# DS157-1_0-B.net
KiCad netlist of a schematic drawn in Altium Designer
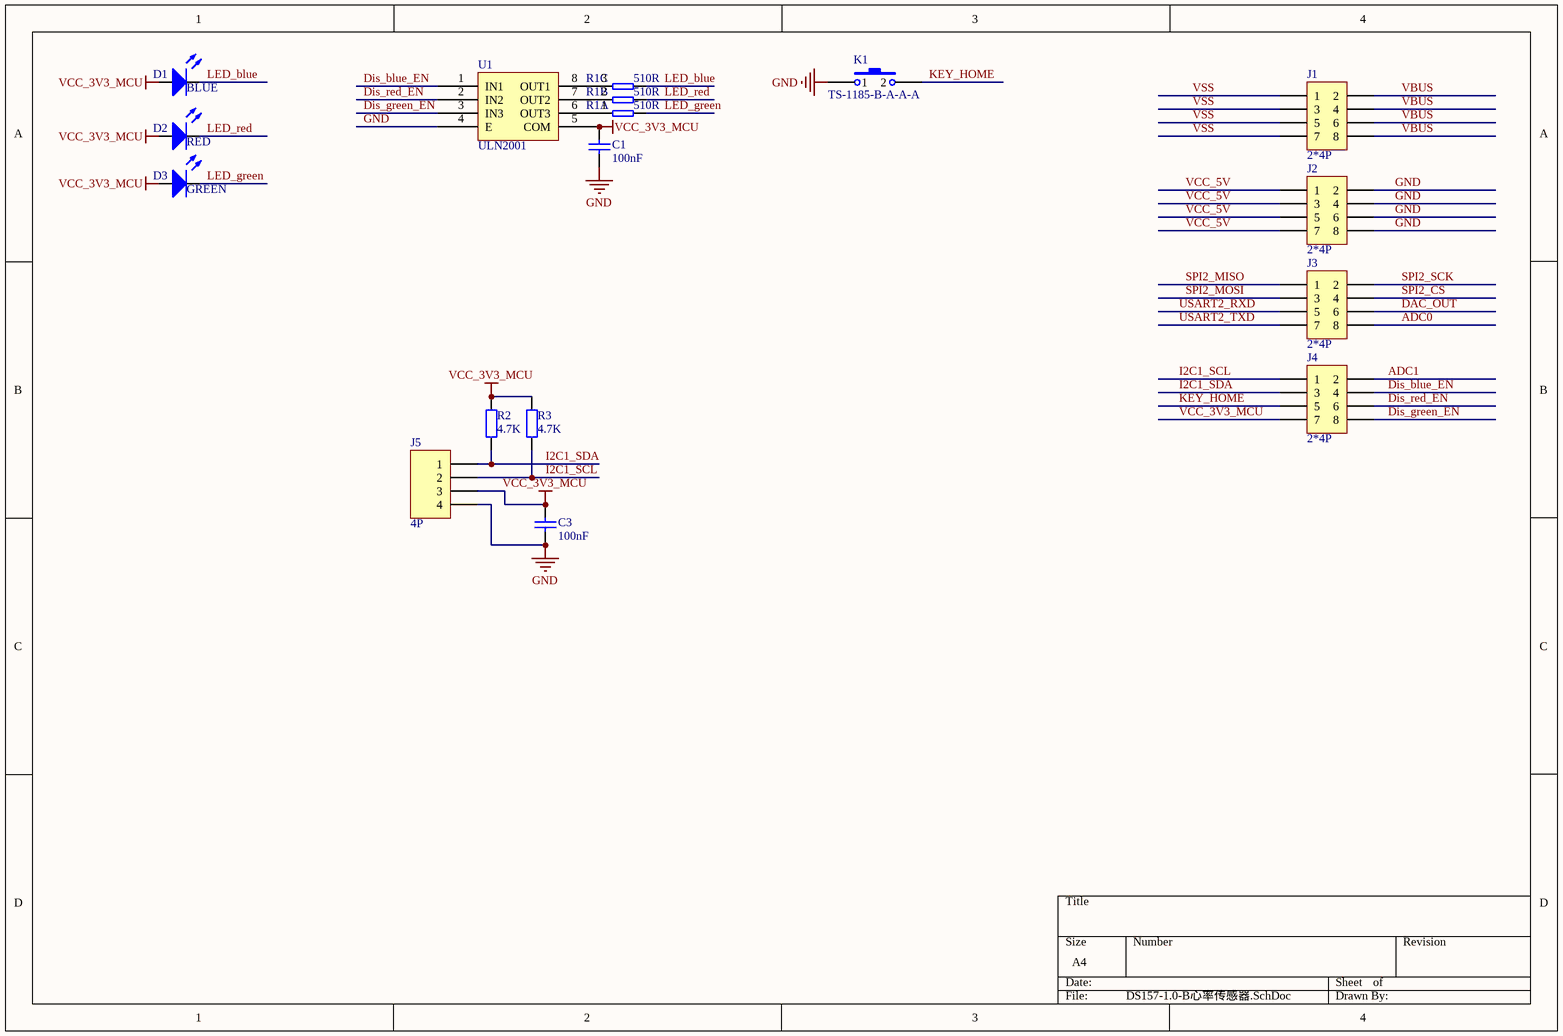
[diagram p0: DS157-1.0-B心率传感器.SchDoc]

(export (version "E")
  (design (tool "Eeschema 10.0.6"))
  (components
    (comp (ref "C1")
      (value "100nF")
      (footprint "0603CAP")
      (description "贴片电容")
      (fields (field (name "Comment") "SMDCAP00013"))
      (libsource (lib "AD_SCH") (part "MLCC 100nF 50V ±10％ 0603"))
    )
    (comp (ref "C3")
      (value "100nF")
      (footprint "0603CAP")
      (description "贴片电容")
      (fields (field (name "Comment") "SMDCAP00013"))
      (libsource (lib "AD_SCH") (part "MLCC 100nF 50V ±10％ 0603"))
    )
    (comp (ref "D1")
      (value "BLUE")
      (footprint "LED_0805")
      (description "贴片LED")
      (fields (field (name "Comment") "SMDLED00010"))
      (libsource (lib "AD_SCH") (part "Chip 蓝色LED 0805"))
    )
    (comp (ref "D2")
      (value "RED")
      (footprint "LED_0805")
      (description "贴片LED")
      (fields (field (name "Comment") "SMDLED00003"))
      (libsource (lib "AD_SCH") (part "Chip 红色LED 0805"))
    )
    (comp (ref "D3")
      (value "GREEN")
      (footprint "LED_0805")
      (description "贴片LED")
      (fields (field (name "Comment") "Chip 翠绿LED 0805"))
      (libsource (lib "AD_SCH") (part "Chip 翠绿LED 0805"))
    )
    (comp (ref "J1")
      (value "2*4P")
      (footprint "X1321WVS-2x04J-C40D53")
      (description "双排针2x4P 立贴 1.27mm")
      (fields (field (name "Comment") "X1321WVS-2x04J-C40D53"))
      (libsource (lib "AD_SCH") (part "X1321WVS-2x04J-C40D53"))
    )
    (comp (ref "J2")
      (value "2*4P")
      (footprint "X1321WVS-2x04J-C40D53")
      (description "双排针2x4P 立贴 1.27mm")
      (fields (field (name "Comment") "X1321WVS-2x04J-C40D53"))
      (libsource (lib "AD_SCH") (part "X1321WVS-2x04J-C40D53"))
    )
    (comp (ref "J3")
      (value "2*4P")
      (footprint "X1321WVS-2x04J-C40D53")
      (description "双排针2x4P 立贴 1.27mm")
      (fields (field (name "Comment") "X1321WVS-2x04J-C40D53"))
      (libsource (lib "AD_SCH") (part "X1321WVS-2x04J-C40D53"))
    )
    (comp (ref "J4")
      (value "2*4P")
      (footprint "X1321WVS-2x04J-C40D53")
      (description "双排针2x4P 立贴 1.27mm")
      (fields (field (name "Comment") "X1321WVS-2x04J-C40D53"))
      (libsource (lib "AD_SCH") (part "X1321WVS-2x04J-C40D53"))
    )
    (comp (ref "J5")
      (value "4P")
      (footprint "SIP4")
      (description "单排母座")
      (fields (field (name "Comment") "SL000000047"))
      (libsource (lib "AD_SCH") (part "DIP4 单排母座 间距2.54mm 铜"))
    )
    (comp (ref "K1")
      (value "TS-1185-B-A-A-A")
      (footprint "KEY_TS-1185-x-A-A-A")
      (description "轻触开关")
      (libsource (lib "AD_SCH") (part "TS-1185-B-A-A-A"))
    )
    (comp (ref "R1")
      (value "510R")
      (footprint "0603RES_Pack4")
      (description "贴片排阻")
      (fields (field (name "Comment") "SMDRES05003"))
      (libsource (lib "AD_SCH") (part "Chip R*4 510R 1/16W ±5％ 0603"))
    )
    (comp (ref "R2")
      (value "4.7K")
      (footprint "0603RES")
      (description "贴片电阻")
      (fields (field (name "Comment") "SMDRES00047"))
      (libsource (lib "AD_SCH") (part "Chip 4.7K 1/16W ±1％ 0603"))
    )
    (comp (ref "R3")
      (value "4.7K")
      (footprint "0603RES")
      (description "贴片电阻")
      (fields (field (name "Comment") "SMDRES00047"))
      (libsource (lib "AD_SCH") (part "Chip 4.7K 1/16W ±1％ 0603"))
    )
    (comp (ref "U1")
      (value "ULN2001")
      (footprint "SO-8")
      (description "电机驱动芯片")
      (fields (field (name "Comment") "SMDIC000018"))
      (libsource (lib "AD_SCH") (part "ULN2001 SOP-8"))
    )
  )
  (nets
    (net (code "1") (name "/ADC0") (class "Default")
      (node (ref "J3") (pin "8") (pinfunction "8_8") (pintype "passive"))
    )
    (net (code "2") (name "/ADC1") (class "Default")
      (node (ref "J4") (pin "2") (pinfunction "2_2") (pintype "passive"))
    )
    (net (code "3") (name "/DAC_OUT") (class "Default")
      (node (ref "J3") (pin "6") (pinfunction "6_6") (pintype "passive"))
    )
    (net (code "4") (name "/Dis_blue_EN") (class "Default")
      (node (ref "J4") (pin "4") (pinfunction "4_4") (pintype "passive"))
      (node (ref "U1") (pin "1") (pinfunction "IN1_1") (pintype "passive"))
    )
    (net (code "5") (name "/Dis_green_EN") (class "Default")
      (node (ref "J4") (pin "8") (pinfunction "8_8") (pintype "passive"))
      (node (ref "U1") (pin "3") (pinfunction "IN3_3") (pintype "passive"))
    )
    (net (code "6") (name "/Dis_red_EN") (class "Default")
      (node (ref "J4") (pin "6") (pinfunction "6_6") (pintype "passive"))
      (node (ref "U1") (pin "2") (pinfunction "IN2_2") (pintype "passive"))
    )
    (net (code "7") (name "/I2C1_SCL") (class "Default")
      (node (ref "J4") (pin "1") (pinfunction "1_1") (pintype "passive"))
      (node (ref "J5") (pin "2") (pinfunction "2_2") (pintype "passive"))
      (node (ref "R3") (pin "1") (pinfunction "1_1") (pintype "passive"))
    )
    (net (code "8") (name "/I2C1_SDA") (class "Default")
      (node (ref "J4") (pin "3") (pinfunction "3_3") (pintype "passive"))
      (node (ref "J5") (pin "1") (pinfunction "1_1") (pintype "passive"))
      (node (ref "R2") (pin "1") (pinfunction "1_1") (pintype "passive"))
    )
    (net (code "9") (name "/KEY_HOME") (class "Default")
      (node (ref "J4") (pin "5") (pinfunction "5_5") (pintype "passive"))
      (node (ref "K1") (pin "2") (pinfunction "2_2") (pintype "passive"))
    )
    (net (code "10") (name "/LED_blue") (class "Default")
      (node (ref "D1") (pin "2") (pinfunction "K_2") (pintype "passive"))
      (node (ref "R1") (pin "6") (pinfunction "6_6") (pintype "passive"))
    )
    (net (code "11") (name "/LED_green") (class "Default")
      (node (ref "D3") (pin "2") (pinfunction "K_2") (pintype "passive"))
      (node (ref "R1") (pin "8") (pinfunction "8_8") (pintype "passive"))
    )
    (net (code "12") (name "/LED_red") (class "Default")
      (node (ref "D2") (pin "2") (pinfunction "K_2") (pintype "passive"))
      (node (ref "R1") (pin "7") (pinfunction "7_7") (pintype "passive"))
    )
    (net (code "13") (name "/SPI2_CS") (class "Default")
      (node (ref "J3") (pin "4") (pinfunction "4_4") (pintype "passive"))
    )
    (net (code "14") (name "/SPI2_MISO") (class "Default")
      (node (ref "J3") (pin "1") (pinfunction "1_1") (pintype "passive"))
    )
    (net (code "15") (name "/SPI2_MOSI") (class "Default")
      (node (ref "J3") (pin "3") (pinfunction "3_3") (pintype "passive"))
    )
    (net (code "16") (name "/SPI2_SCK") (class "Default")
      (node (ref "J3") (pin "2") (pinfunction "2_2") (pintype "passive"))
    )
    (net (code "17") (name "/USART2_RXD") (class "Default")
      (node (ref "J3") (pin "5") (pinfunction "5_5") (pintype "passive"))
    )
    (net (code "18") (name "/USART2_TXD") (class "Default")
      (node (ref "J3") (pin "7") (pinfunction "7_7") (pintype "passive"))
    )
    (net (code "19") (name "/VBUS") (class "Default")
      (node (ref "J1") (pin "2") (pinfunction "2_2") (pintype "passive"))
      (node (ref "J1") (pin "4") (pinfunction "4_4") (pintype "passive"))
      (node (ref "J1") (pin "6") (pinfunction "6_6") (pintype "passive"))
      (node (ref "J1") (pin "8") (pinfunction "8_8") (pintype "passive"))
    )
    (net (code "20") (name "/VCC_5V") (class "Default")
      (node (ref "J2") (pin "1") (pinfunction "1_1") (pintype "passive"))
      (node (ref "J2") (pin "3") (pinfunction "3_3") (pintype "passive"))
      (node (ref "J2") (pin "5") (pinfunction "5_5") (pintype "passive"))
      (node (ref "J2") (pin "7") (pinfunction "7_7") (pintype "passive"))
    )
    (net (code "21") (name "/VSS") (class "Default")
      (node (ref "J1") (pin "1") (pinfunction "1_1") (pintype "passive"))
      (node (ref "J1") (pin "3") (pinfunction "3_3") (pintype "passive"))
      (node (ref "J1") (pin "5") (pinfunction "5_5") (pintype "passive"))
      (node (ref "J1") (pin "7") (pinfunction "7_7") (pintype "passive"))
    )
    (net (code "22") (name "GND") (class "Default")
      (node (ref "C1") (pin "1") (pinfunction "1_1") (pintype "passive"))
      (node (ref "C3") (pin "1") (pinfunction "1_1") (pintype "passive"))
      (node (ref "J2") (pin "2") (pinfunction "2_2") (pintype "passive"))
      (node (ref "J2") (pin "4") (pinfunction "4_4") (pintype "passive"))
      (node (ref "J2") (pin "6") (pinfunction "6_6") (pintype "passive"))
      (node (ref "J2") (pin "8") (pinfunction "8_8") (pintype "passive"))
      (node (ref "J5") (pin "4") (pinfunction "4_4") (pintype "passive"))
      (node (ref "K1") (pin "1") (pinfunction "1_1") (pintype "passive"))
      (node (ref "U1") (pin "4") (pinfunction "E_4") (pintype "passive"))
    )
    (net (code "23") (name "Net-(U1-OUT1)") (class "Default")
      (node (ref "R1") (pin "3") (pinfunction "3_3") (pintype "passive"))
      (node (ref "U1") (pin "8") (pinfunction "OUT1_8") (pintype "passive"))
    )
    (net (code "24") (name "Net-(U1-OUT2)") (class "Default")
      (node (ref "R1") (pin "2") (pinfunction "2_2") (pintype "passive"))
      (node (ref "U1") (pin "7") (pinfunction "OUT2_7") (pintype "passive"))
    )
    (net (code "25") (name "Net-(U1-OUT3)") (class "Default")
      (node (ref "R1") (pin "1") (pinfunction "1_1") (pintype "passive"))
      (node (ref "U1") (pin "6") (pinfunction "OUT3_6") (pintype "passive"))
    )
    (net (code "26") (name "VCC_3V3_MCU") (class "Default")
      (node (ref "C1") (pin "2") (pinfunction "2_2") (pintype "passive"))
      (node (ref "C3") (pin "2") (pinfunction "2_2") (pintype "passive"))
      (node (ref "D1") (pin "1") (pinfunction "A_1") (pintype "passive"))
      (node (ref "D2") (pin "1") (pinfunction "A_1") (pintype "passive"))
      (node (ref "D3") (pin "1") (pinfunction "A_1") (pintype "passive"))
      (node (ref "J4") (pin "7") (pinfunction "7_7") (pintype "passive"))
      (node (ref "J5") (pin "3") (pinfunction "3_3") (pintype "passive"))
      (node (ref "R2") (pin "2") (pinfunction "2_2") (pintype "passive"))
      (node (ref "R3") (pin "2") (pinfunction "2_2") (pintype "passive"))
      (node (ref "U1") (pin "5") (pinfunction "COM_5") (pintype "passive"))
    )
  )
)
